# untitled.net
KiCad netlist of a schematic drawn in EAGLE
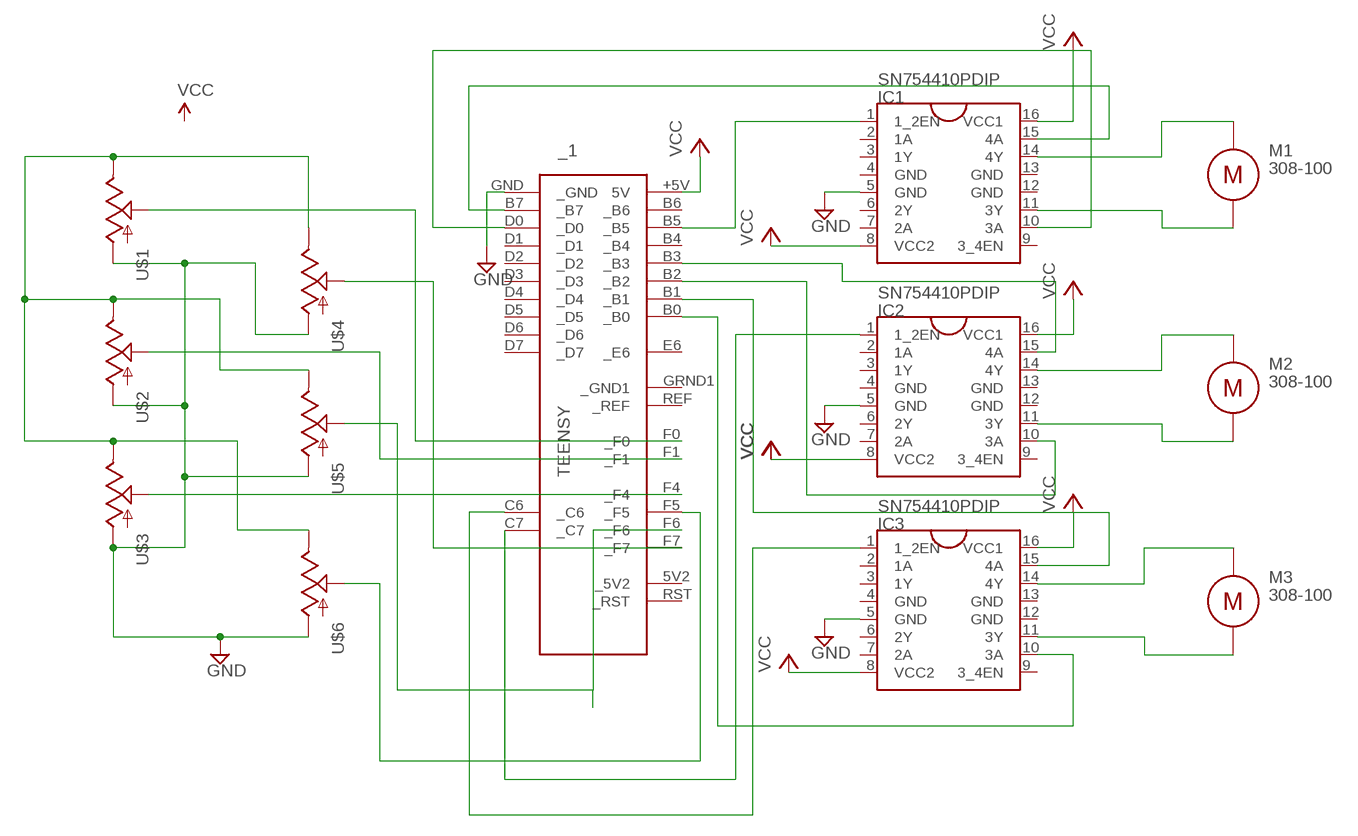
[diagram p0: schematic, sheet 1]

(export (version "E")
  (design (tool "Eeschema 10.0.6"))
  (components
    (comp (ref "IC1")
      (value "SN754410PDIP")
      (footprint "eagle-import:DIL16")
      (libsource (lib "eagle-import") (part "SN754410PDIP"))
    )
    (comp (ref "IC2")
      (value "SN754410PDIP")
      (footprint "eagle-import:DIL16")
      (libsource (lib "eagle-import") (part "SN754410PDIP"))
    )
    (comp (ref "IC3")
      (value "SN754410PDIP")
      (footprint "eagle-import:DIL16")
      (libsource (lib "eagle-import") (part "SN754410PDIP"))
    )
    (comp (ref "M1")
      (value "308-100")
      (footprint "eagle-import:308-100")
      (libsource (lib "eagle-import") (part "308-100"))
    )
    (comp (ref "M2")
      (value "308-100")
      (footprint "eagle-import:308-100")
      (libsource (lib "eagle-import") (part "308-100"))
    )
    (comp (ref "M3")
      (value "308-100")
      (footprint "eagle-import:308-100")
      (libsource (lib "eagle-import") (part "308-100"))
    )
    (comp (ref "U$1")
      (value "POT")
      (footprint "eagle-import:ALPS_POT")
      (libsource (lib "eagle-import") (part "POT"))
    )
    (comp (ref "U$2")
      (value "POT")
      (footprint "eagle-import:ALPS_POT")
      (libsource (lib "eagle-import") (part "POT"))
    )
    (comp (ref "U$3")
      (value "POT")
      (footprint "eagle-import:ALPS_POT")
      (libsource (lib "eagle-import") (part "POT"))
    )
    (comp (ref "U$4")
      (value "POT")
      (footprint "eagle-import:ALPS_POT")
      (libsource (lib "eagle-import") (part "POT"))
    )
    (comp (ref "U$5")
      (value "POT")
      (footprint "eagle-import:ALPS_POT")
      (libsource (lib "eagle-import") (part "POT"))
    )
    (comp (ref "U$6")
      (value "POT")
      (footprint "eagle-import:ALPS_POT")
      (libsource (lib "eagle-import") (part "POT"))
    )
    (comp (ref "_1")
      (value "TEENSY")
      (footprint "eagle-import:TEENSY")
      (libsource (lib "eagle-import") (part "TEENSY"))
    )
  )
  (nets
    (net (code "1") (name "GND") (class "Default")
      (node (ref "IC1") (pin "5") (pinfunction "GND_5") (pintype "bidirectional"))
      (node (ref "IC2") (pin "5") (pinfunction "GND_5") (pintype "bidirectional"))
      (node (ref "IC3") (pin "5") (pinfunction "GND_5") (pintype "bidirectional"))
      (node (ref "U$1") (pin "P$3") (pinfunction "A_P$3") (pintype "passive"))
      (node (ref "U$2") (pin "P$3") (pinfunction "A_P$3") (pintype "passive"))
      (node (ref "U$3") (pin "P$3") (pinfunction "A_P$3") (pintype "passive"))
      (node (ref "U$4") (pin "P$3") (pinfunction "A_P$3") (pintype "passive"))
      (node (ref "U$5") (pin "P$3") (pinfunction "A_P$3") (pintype "passive"))
      (node (ref "U$6") (pin "P$3") (pinfunction "A_P$3") (pintype "passive"))
      (node (ref "_1") (pin "GND") (pinfunction "_GND_GND") (pintype "bidirectional"))
    )
    (net (code "2") (name "Net-(IC1-1_2EN)") (class "Default")
      (node (ref "IC1") (pin "1") (pinfunction "1_2EN_1") (pintype "bidirectional"))
      (node (ref "_1") (pin "B5") (pinfunction "_B5_B5") (pintype "bidirectional"))
    )
    (net (code "3") (name "Net-(IC1-3A)") (class "Default")
      (node (ref "IC1") (pin "10") (pinfunction "3A_10") (pintype "bidirectional"))
      (node (ref "_1") (pin "D0") (pinfunction "_D0_D0") (pintype "bidirectional"))
    )
    (net (code "4") (name "Net-(IC1-3Y)") (class "Default")
      (node (ref "IC1") (pin "11") (pinfunction "3Y_11") (pintype "bidirectional"))
      (node (ref "M1") (pin "NEG") (pinfunction "NEG_NEG") (pintype "bidirectional"))
    )
    (net (code "5") (name "Net-(IC1-4A)") (class "Default")
      (node (ref "IC1") (pin "15") (pinfunction "4A_15") (pintype "bidirectional"))
      (node (ref "_1") (pin "B7") (pinfunction "_B7_B7") (pintype "bidirectional"))
    )
    (net (code "6") (name "Net-(IC1-4Y)") (class "Default")
      (node (ref "IC1") (pin "14") (pinfunction "4Y_14") (pintype "bidirectional"))
      (node (ref "M1") (pin "POS") (pinfunction "POS_POS") (pintype "bidirectional"))
    )
    (net (code "7") (name "Net-(IC2-1_2EN)") (class "Default")
      (node (ref "IC2") (pin "1") (pinfunction "1_2EN_1") (pintype "bidirectional"))
      (node (ref "_1") (pin "C7") (pinfunction "_C7_C7") (pintype "bidirectional"))
    )
    (net (code "8") (name "Net-(IC2-3A)") (class "Default")
      (node (ref "IC2") (pin "10") (pinfunction "3A_10") (pintype "bidirectional"))
      (node (ref "_1") (pin "B2") (pinfunction "_B2_B2") (pintype "bidirectional"))
    )
    (net (code "9") (name "Net-(IC2-3Y)") (class "Default")
      (node (ref "IC2") (pin "11") (pinfunction "3Y_11") (pintype "bidirectional"))
      (node (ref "M2") (pin "NEG") (pinfunction "NEG_NEG") (pintype "bidirectional"))
    )
    (net (code "10") (name "Net-(IC2-4A)") (class "Default")
      (node (ref "IC2") (pin "15") (pinfunction "4A_15") (pintype "bidirectional"))
      (node (ref "_1") (pin "B3") (pinfunction "_B3_B3") (pintype "bidirectional"))
    )
    (net (code "11") (name "Net-(IC2-4Y)") (class "Default")
      (node (ref "IC2") (pin "14") (pinfunction "4Y_14") (pintype "bidirectional"))
      (node (ref "M2") (pin "POS") (pinfunction "POS_POS") (pintype "bidirectional"))
    )
    (net (code "12") (name "Net-(IC3-1_2EN)") (class "Default")
      (node (ref "IC3") (pin "1") (pinfunction "1_2EN_1") (pintype "bidirectional"))
      (node (ref "_1") (pin "C6") (pinfunction "_C6_C6") (pintype "bidirectional"))
    )
    (net (code "13") (name "Net-(IC3-3A)") (class "Default")
      (node (ref "IC3") (pin "10") (pinfunction "3A_10") (pintype "bidirectional"))
      (node (ref "_1") (pin "B0") (pinfunction "_B0_B0") (pintype "bidirectional"))
    )
    (net (code "14") (name "Net-(IC3-3Y)") (class "Default")
      (node (ref "IC3") (pin "11") (pinfunction "3Y_11") (pintype "bidirectional"))
      (node (ref "M3") (pin "NEG") (pinfunction "NEG_NEG") (pintype "bidirectional"))
    )
    (net (code "15") (name "Net-(IC3-4A)") (class "Default")
      (node (ref "IC3") (pin "15") (pinfunction "4A_15") (pintype "bidirectional"))
      (node (ref "_1") (pin "B1") (pinfunction "_B1_B1") (pintype "bidirectional"))
    )
    (net (code "16") (name "Net-(IC3-4Y)") (class "Default")
      (node (ref "IC3") (pin "14") (pinfunction "4Y_14") (pintype "bidirectional"))
      (node (ref "M3") (pin "POS") (pinfunction "POS_POS") (pintype "bidirectional"))
    )
    (net (code "17") (name "Net-(U$1-E)") (class "Default")
      (node (ref "U$1") (pin "P$1") (pinfunction "E_P$1") (pintype "passive"))
      (node (ref "U$2") (pin "P$1") (pinfunction "E_P$1") (pintype "passive"))
      (node (ref "U$3") (pin "P$1") (pinfunction "E_P$1") (pintype "passive"))
      (node (ref "U$4") (pin "P$1") (pinfunction "E_P$1") (pintype "passive"))
      (node (ref "U$5") (pin "P$1") (pinfunction "E_P$1") (pintype "passive"))
      (node (ref "U$6") (pin "P$1") (pinfunction "E_P$1") (pintype "passive"))
    )
    (net (code "18") (name "Net-(U$1-S)") (class "Default")
      (node (ref "U$1") (pin "P$2") (pinfunction "S_P$2") (pintype "passive"))
      (node (ref "_1") (pin "F0") (pinfunction "_F0_F0") (pintype "bidirectional"))
    )
    (net (code "19") (name "Net-(U$2-S)") (class "Default")
      (node (ref "U$2") (pin "P$2") (pinfunction "S_P$2") (pintype "passive"))
      (node (ref "_1") (pin "F1") (pinfunction "_F1_F1") (pintype "bidirectional"))
    )
    (net (code "20") (name "Net-(U$3-S)") (class "Default")
      (node (ref "U$3") (pin "P$2") (pinfunction "S_P$2") (pintype "passive"))
      (node (ref "_1") (pin "F4") (pinfunction "_F4_F4") (pintype "bidirectional"))
    )
    (net (code "21") (name "Net-(U$4-S)") (class "Default")
      (node (ref "U$4") (pin "P$2") (pinfunction "S_P$2") (pintype "passive"))
      (node (ref "_1") (pin "F7") (pinfunction "_F7_F7") (pintype "bidirectional"))
    )
    (net (code "22") (name "Net-(U$5-S)") (class "Default")
      (node (ref "U$5") (pin "P$2") (pinfunction "S_P$2") (pintype "passive"))
      (node (ref "_1") (pin "F6") (pinfunction "_F6_F6") (pintype "bidirectional"))
    )
    (net (code "23") (name "Net-(U$6-S)") (class "Default")
      (node (ref "U$6") (pin "P$2") (pinfunction "S_P$2") (pintype "passive"))
      (node (ref "_1") (pin "F5") (pinfunction "_F5_F5") (pintype "bidirectional"))
    )
    (net (code "24") (name "VCC") (class "Default")
      (node (ref "IC1") (pin "16") (pinfunction "VCC1_16") (pintype "bidirectional"))
      (node (ref "IC1") (pin "8") (pinfunction "VCC2_8") (pintype "bidirectional"))
      (node (ref "IC2") (pin "16") (pinfunction "VCC1_16") (pintype "bidirectional"))
      (node (ref "IC2") (pin "8") (pinfunction "VCC2_8") (pintype "bidirectional"))
      (node (ref "IC3") (pin "16") (pinfunction "VCC1_16") (pintype "bidirectional"))
      (node (ref "IC3") (pin "8") (pinfunction "VCC2_8") (pintype "bidirectional"))
      (node (ref "_1") (pin "+5V") (pinfunction "5V_+5V") (pintype "bidirectional"))
    )
    (net (code "25") (name "unconnected-(IC1-1A-Pad2)") (class "Default")
      (node (ref "IC1") (pin "2") (pinfunction "1A_2") (pintype "bidirectional"))
    )
    (net (code "26") (name "unconnected-(IC1-1Y-Pad3)") (class "Default")
      (node (ref "IC1") (pin "3") (pinfunction "1Y_3") (pintype "bidirectional"))
    )
    (net (code "27") (name "unconnected-(IC1-2A-Pad7)") (class "Default")
      (node (ref "IC1") (pin "7") (pinfunction "2A_7") (pintype "bidirectional"))
    )
    (net (code "28") (name "unconnected-(IC1-2Y-Pad6)") (class "Default")
      (node (ref "IC1") (pin "6") (pinfunction "2Y_6") (pintype "bidirectional"))
    )
    (net (code "29") (name "unconnected-(IC1-3_4EN-Pad9)") (class "Default")
      (node (ref "IC1") (pin "9") (pinfunction "3_4EN_9") (pintype "bidirectional"))
    )
    (net (code "30") (name "unconnected-(IC1-GND-Pad4)") (class "Default")
      (node (ref "IC1") (pin "4") (pinfunction "GND_4") (pintype "bidirectional"))
    )
    (net (code "31") (name "unconnected-(IC1-GND-Pad12)") (class "Default")
      (node (ref "IC1") (pin "12") (pinfunction "GND_12") (pintype "bidirectional"))
    )
    (net (code "32") (name "unconnected-(IC1-GND-Pad13)") (class "Default")
      (node (ref "IC1") (pin "13") (pinfunction "GND_13") (pintype "bidirectional"))
    )
    (net (code "33") (name "unconnected-(IC2-1A-Pad2)") (class "Default")
      (node (ref "IC2") (pin "2") (pinfunction "1A_2") (pintype "bidirectional"))
    )
    (net (code "34") (name "unconnected-(IC2-1Y-Pad3)") (class "Default")
      (node (ref "IC2") (pin "3") (pinfunction "1Y_3") (pintype "bidirectional"))
    )
    (net (code "35") (name "unconnected-(IC2-2A-Pad7)") (class "Default")
      (node (ref "IC2") (pin "7") (pinfunction "2A_7") (pintype "bidirectional"))
    )
    (net (code "36") (name "unconnected-(IC2-2Y-Pad6)") (class "Default")
      (node (ref "IC2") (pin "6") (pinfunction "2Y_6") (pintype "bidirectional"))
    )
    (net (code "37") (name "unconnected-(IC2-3_4EN-Pad9)") (class "Default")
      (node (ref "IC2") (pin "9") (pinfunction "3_4EN_9") (pintype "bidirectional"))
    )
    (net (code "38") (name "unconnected-(IC2-GND-Pad4)") (class "Default")
      (node (ref "IC2") (pin "4") (pinfunction "GND_4") (pintype "bidirectional"))
    )
    (net (code "39") (name "unconnected-(IC2-GND-Pad12)") (class "Default")
      (node (ref "IC2") (pin "12") (pinfunction "GND_12") (pintype "bidirectional"))
    )
    (net (code "40") (name "unconnected-(IC2-GND-Pad13)") (class "Default")
      (node (ref "IC2") (pin "13") (pinfunction "GND_13") (pintype "bidirectional"))
    )
    (net (code "41") (name "unconnected-(IC3-1A-Pad2)") (class "Default")
      (node (ref "IC3") (pin "2") (pinfunction "1A_2") (pintype "bidirectional"))
    )
    (net (code "42") (name "unconnected-(IC3-1Y-Pad3)") (class "Default")
      (node (ref "IC3") (pin "3") (pinfunction "1Y_3") (pintype "bidirectional"))
    )
    (net (code "43") (name "unconnected-(IC3-2A-Pad7)") (class "Default")
      (node (ref "IC3") (pin "7") (pinfunction "2A_7") (pintype "bidirectional"))
    )
    (net (code "44") (name "unconnected-(IC3-2Y-Pad6)") (class "Default")
      (node (ref "IC3") (pin "6") (pinfunction "2Y_6") (pintype "bidirectional"))
    )
    (net (code "45") (name "unconnected-(IC3-3_4EN-Pad9)") (class "Default")
      (node (ref "IC3") (pin "9") (pinfunction "3_4EN_9") (pintype "bidirectional"))
    )
    (net (code "46") (name "unconnected-(IC3-GND-Pad4)") (class "Default")
      (node (ref "IC3") (pin "4") (pinfunction "GND_4") (pintype "bidirectional"))
    )
    (net (code "47") (name "unconnected-(IC3-GND-Pad12)") (class "Default")
      (node (ref "IC3") (pin "12") (pinfunction "GND_12") (pintype "bidirectional"))
    )
    (net (code "48") (name "unconnected-(IC3-GND-Pad13)") (class "Default")
      (node (ref "IC3") (pin "13") (pinfunction "GND_13") (pintype "bidirectional"))
    )
    (net (code "49") (name "unconnected-(_1-_5V2-Pad5V2)") (class "Default")
      (node (ref "_1") (pin "5V2") (pinfunction "_5V2_5V2") (pintype "bidirectional"))
    )
    (net (code "50") (name "unconnected-(_1-_B4-PadB4)") (class "Default")
      (node (ref "_1") (pin "B4") (pinfunction "_B4_B4") (pintype "bidirectional"))
    )
    (net (code "51") (name "unconnected-(_1-_B6-PadB6)") (class "Default")
      (node (ref "_1") (pin "B6") (pinfunction "_B6_B6") (pintype "bidirectional"))
    )
    (net (code "52") (name "unconnected-(_1-_D1-PadD1)") (class "Default")
      (node (ref "_1") (pin "D1") (pinfunction "_D1_D1") (pintype "bidirectional"))
    )
    (net (code "53") (name "unconnected-(_1-_D2-PadD2)") (class "Default")
      (node (ref "_1") (pin "D2") (pinfunction "_D2_D2") (pintype "bidirectional"))
    )
    (net (code "54") (name "unconnected-(_1-_D3-PadD3)") (class "Default")
      (node (ref "_1") (pin "D3") (pinfunction "_D3_D3") (pintype "bidirectional"))
    )
    (net (code "55") (name "unconnected-(_1-_D4-PadD4)") (class "Default")
      (node (ref "_1") (pin "D4") (pinfunction "_D4_D4") (pintype "bidirectional"))
    )
    (net (code "56") (name "unconnected-(_1-_D5-PadD5)") (class "Default")
      (node (ref "_1") (pin "D5") (pinfunction "_D5_D5") (pintype "bidirectional"))
    )
    (net (code "57") (name "unconnected-(_1-_D6-PadD6)") (class "Default")
      (node (ref "_1") (pin "D6") (pinfunction "_D6_D6") (pintype "bidirectional"))
    )
    (net (code "58") (name "unconnected-(_1-_D7-PadD7)") (class "Default")
      (node (ref "_1") (pin "D7") (pinfunction "_D7_D7") (pintype "bidirectional"))
    )
    (net (code "59") (name "unconnected-(_1-_E6-PadE6)") (class "Default")
      (node (ref "_1") (pin "E6") (pinfunction "_E6_E6") (pintype "bidirectional"))
    )
    (net (code "60") (name "unconnected-(_1-_GND1-PadGRND1)") (class "Default")
      (node (ref "_1") (pin "GRND1") (pinfunction "_GND1_GRND1") (pintype "bidirectional"))
    )
    (net (code "61") (name "unconnected-(_1-_REF-PadREF)") (class "Default")
      (node (ref "_1") (pin "REF") (pinfunction "_REF_REF") (pintype "bidirectional"))
    )
    (net (code "62") (name "unconnected-(_1-_RST-PadRST)") (class "Default")
      (node (ref "_1") (pin "RST") (pinfunction "_RST_RST") (pintype "bidirectional"))
    )
  )
)
